# Microcontroller_STM32F101.net
KiCad netlist of a schematic drawn in Altium Designer
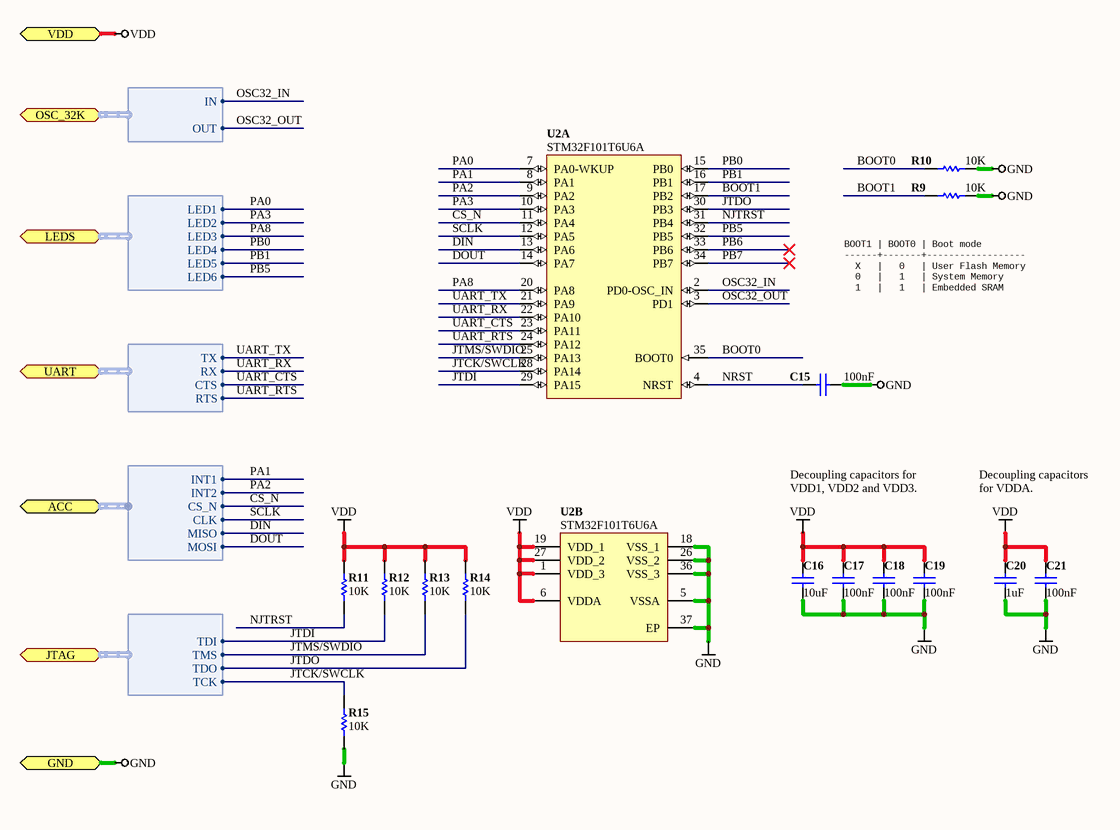
[diagram p0: Microcontroller_STM32F101.SchDoc]

(export (version "E")
  (design (tool "Eeschema 10.0.6"))
  (components
    (comp (ref "C15")
      (value "100nF")
      (footprint "CAPC0402(1005)60_N")
      (description "CAP 100nF 6.3V ±5% 0402 (1005 Metric) Thickness 0.6mm SMD")
      (fields (field (name "TOLERANCE") "±5%") (field (name "Comment") "CAP 100nF 6.3V 0402(1005)"))
      (libsource (lib "Altium Content Vault") (part "CMP-1034-02060-1"))
    )
    (comp (ref "C16")
      (value "10uF")
      (footprint "CAPC0603(1608)100_N")
      (description "CAP 10uF 10V ±20% 0603 (1608 Metric) Thickness 1mm SMD")
      (fields (field (name "TOLERANCE") "±20%") (field (name "Comment") "CAP 10uF 10V 0603(1608)"))
      (libsource (lib "Altium Content Vault") (part "CMP-1035-02800-1"))
    )
    (comp (ref "C17")
      (value "100nF")
      (footprint "CAPC0402(1005)60_N")
      (description "CAP 100nF 6.3V ±5% 0402 (1005 Metric) Thickness 0.6mm SMD")
      (fields (field (name "TOLERANCE") "±5%") (field (name "Comment") "CAP 100nF 6.3V 0402(1005)"))
      (libsource (lib "Altium Content Vault") (part "CMP-1034-02060-1"))
    )
    (comp (ref "C18")
      (value "100nF")
      (footprint "CAPC0402(1005)60_N")
      (description "CAP 100nF 6.3V ±5% 0402 (1005 Metric) Thickness 0.6mm SMD")
      (fields (field (name "TOLERANCE") "±5%") (field (name "Comment") "CAP 100nF 6.3V 0402(1005)"))
      (libsource (lib "Altium Content Vault") (part "CMP-1034-02060-1"))
    )
    (comp (ref "C19")
      (value "100nF")
      (footprint "CAPC0402(1005)60_N")
      (description "CAP 100nF 6.3V ±5% 0402 (1005 Metric) Thickness 0.6mm SMD")
      (fields (field (name "TOLERANCE") "±5%") (field (name "Comment") "CAP 100nF 6.3V 0402(1005)"))
      (libsource (lib "Altium Content Vault") (part "CMP-1034-02060-1"))
    )
    (comp (ref "C20")
      (value "1uF")
      (footprint "CAPC0402(1005)60_N")
      (description "CAP 1uF 6.3V ±10% 0402 (1005 Metric) Thickness 0.6mm SMD")
      (fields (field (name "TOLERANCE") "±10%") (field (name "Comment") "CAP 1uF 6.3V 0402(1005)"))
      (libsource (lib "Altium Content Vault") (part "CMP-1034-02113-1"))
    )
    (comp (ref "C21")
      (value "100nF")
      (footprint "CAPC0402(1005)60_N")
      (description "CAP 100nF 6.3V ±5% 0402 (1005 Metric) Thickness 0.6mm SMD")
      (fields (field (name "TOLERANCE") "±5%") (field (name "Comment") "CAP 100nF 6.3V 0402(1005)"))
      (libsource (lib "Altium Content Vault") (part "CMP-1034-02060-1"))
    )
    (comp (ref "R9")
      (value "10K")
      (footprint "RESC0402(1005)_N")
      (description "10K 0.063W 5% 0402 (1005 Metric)  SMD")
      (fields (field (name "TOLERANCE") "5 %") (field (name "POWER") "0.063 W"))
      (libsource (lib "Altium Content Vault") (part "CMP-1011-00098-1"))
    )
    (comp (ref "R10")
      (value "10K")
      (footprint "RESC0402(1005)_N")
      (description "10K 0.063W 5% 0402 (1005 Metric)  SMD")
      (fields (field (name "TOLERANCE") "5 %") (field (name "POWER") "0.063 W"))
      (libsource (lib "Altium Content Vault") (part "CMP-1011-00098-1"))
    )
    (comp (ref "R11")
      (value "10K")
      (footprint "RESC0402(1005)_N")
      (description "10K 0.063W 5% 0402 (1005 Metric)  SMD")
      (fields (field (name "TOLERANCE") "5 %") (field (name "POWER") "0.063 W"))
      (libsource (lib "Altium Content Vault") (part "CMP-1011-00098-1"))
    )
    (comp (ref "R12")
      (value "10K")
      (footprint "RESC0402(1005)_N")
      (description "10K 0.063W 5% 0402 (1005 Metric)  SMD")
      (fields (field (name "TOLERANCE") "5 %") (field (name "POWER") "0.063 W"))
      (libsource (lib "Altium Content Vault") (part "CMP-1011-00098-1"))
    )
    (comp (ref "R13")
      (value "10K")
      (footprint "RESC0402(1005)_N")
      (description "10K 0.063W 5% 0402 (1005 Metric)  SMD")
      (fields (field (name "TOLERANCE") "5 %") (field (name "POWER") "0.063 W"))
      (libsource (lib "Altium Content Vault") (part "CMP-1011-00098-1"))
    )
    (comp (ref "R14")
      (value "10K")
      (footprint "RESC0402(1005)_N")
      (description "10K 0.063W 5% 0402 (1005 Metric)  SMD")
      (fields (field (name "TOLERANCE") "5 %") (field (name "POWER") "0.063 W"))
      (libsource (lib "Altium Content Vault") (part "CMP-1011-00098-1"))
    )
    (comp (ref "R15")
      (value "10K")
      (footprint "RESC0402(1005)_N")
      (description "10K 0.063W 5% 0402 (1005 Metric)  SMD")
      (fields (field (name "TOLERANCE") "5 %") (field (name "POWER") "0.063 W"))
      (libsource (lib "Altium Content Vault") (part "CMP-1011-00098-1"))
    )
    (comp (ref "U2")
      (value "STM32F101T6U6A")
      (footprint "VFQFPN36_N")
      (libsource (lib "Altium Content Vault") (part "MC-ARM-STM32F101-SQ37"))
    )
  )
  (nets
    (net (code "6") (name "/BOOT0") (class "Default")
      (node (ref "R10") (pin "1") (pinfunction "1_1") (pintype "passive"))
      (node (ref "U2") (pin "35") (pinfunction "BOOT0_35") (pintype "input"))
    )
    (net (code "7") (name "/BOOT1") (class "Default")
      (node (ref "R9") (pin "1") (pinfunction "1_1") (pintype "passive"))
      (node (ref "U2") (pin "17") (pinfunction "PB2_17") (pintype "bidirectional"))
    )
    (net (code "8") (name "/CS_N") (class "Default")
      (node (ref "U2") (pin "11") (pinfunction "PA4_11") (pintype "bidirectional"))
    )
    (net (code "9") (name "/DIN") (class "Default")
      (node (ref "U2") (pin "13") (pinfunction "PA6_13") (pintype "bidirectional"))
    )
    (net (code "10") (name "/DOUT") (class "Default")
      (node (ref "U2") (pin "14") (pinfunction "PA7_14") (pintype "bidirectional"))
    )
    (net (code "11") (name "/JTCK{slash}SWCLK") (class "Default")
      (node (ref "R15") (pin "2") (pinfunction "2_2") (pintype "passive"))
      (node (ref "U2") (pin "28") (pinfunction "PA14_28") (pintype "bidirectional"))
    )
    (net (code "12") (name "/JTDI") (class "Default")
      (node (ref "R12") (pin "1") (pinfunction "1_1") (pintype "passive"))
      (node (ref "U2") (pin "29") (pinfunction "PA15_29") (pintype "bidirectional"))
    )
    (net (code "13") (name "/JTDO") (class "Default")
      (node (ref "R14") (pin "1") (pinfunction "1_1") (pintype "passive"))
      (node (ref "U2") (pin "30") (pinfunction "PB3_30") (pintype "bidirectional"))
    )
    (net (code "14") (name "/JTMS{slash}SWDIO") (class "Default")
      (node (ref "R13") (pin "1") (pinfunction "1_1") (pintype "passive"))
      (node (ref "U2") (pin "25") (pinfunction "PA13_25") (pintype "bidirectional"))
    )
    (net (code "15") (name "/NJTRST") (class "Default")
      (node (ref "R11") (pin "1") (pinfunction "1_1") (pintype "passive"))
      (node (ref "U2") (pin "31") (pinfunction "PB4_31") (pintype "bidirectional"))
    )
    (net (code "16") (name "/NRST") (class "Default")
      (node (ref "C15") (pin "1") (pinfunction "1_1") (pintype "passive"))
      (node (ref "U2") (pin "4") (pinfunction "NRST_4") (pintype "bidirectional"))
    )
    (net (code "17") (name "/OSC32_IN") (class "Default")
      (node (ref "U2") (pin "2") (pinfunction "PD0-OSC_IN_2") (pintype "bidirectional"))
    )
    (net (code "18") (name "/OSC32_OUT") (class "Default")
      (node (ref "U2") (pin "3") (pinfunction "PD1_3") (pintype "bidirectional"))
    )
    (net (code "19") (name "/PA0") (class "Default")
      (node (ref "U2") (pin "7") (pinfunction "PA0-WKUP_7") (pintype "bidirectional"))
    )
    (net (code "20") (name "/PA1") (class "Default")
      (node (ref "U2") (pin "8") (pinfunction "PA1_8") (pintype "bidirectional"))
    )
    (net (code "21") (name "/PA2") (class "Default")
      (node (ref "U2") (pin "9") (pinfunction "PA2_9") (pintype "bidirectional"))
    )
    (net (code "22") (name "/PA3") (class "Default")
      (node (ref "U2") (pin "10") (pinfunction "PA3_10") (pintype "bidirectional"))
    )
    (net (code "23") (name "/PA8") (class "Default")
      (node (ref "U2") (pin "20") (pinfunction "PA8_20") (pintype "bidirectional"))
    )
    (net (code "24") (name "/PB0") (class "Default")
      (node (ref "U2") (pin "15") (pinfunction "PB0_15") (pintype "bidirectional"))
    )
    (net (code "25") (name "/PB1") (class "Default")
      (node (ref "U2") (pin "16") (pinfunction "PB1_16") (pintype "bidirectional"))
    )
    (net (code "26") (name "/PB5") (class "Default")
      (node (ref "U2") (pin "32") (pinfunction "PB5_32") (pintype "bidirectional"))
    )
    (net (code "27") (name "/PB6") (class "Default")
      (node (ref "U2") (pin "33") (pinfunction "PB6_33") (pintype "bidirectional+no_connect"))
    )
    (net (code "28") (name "/PB7") (class "Default")
      (node (ref "U2") (pin "34") (pinfunction "PB7_34") (pintype "bidirectional+no_connect"))
    )
    (net (code "29") (name "/SCLK") (class "Default")
      (node (ref "U2") (pin "12") (pinfunction "PA5_12") (pintype "bidirectional"))
    )
    (net (code "30") (name "/UART_CTS") (class "Default")
      (node (ref "U2") (pin "23") (pinfunction "PA11_23") (pintype "bidirectional"))
    )
    (net (code "31") (name "/UART_RTS") (class "Default")
      (node (ref "U2") (pin "24") (pinfunction "PA12_24") (pintype "bidirectional"))
    )
    (net (code "32") (name "/UART_RX") (class "Default")
      (node (ref "U2") (pin "22") (pinfunction "PA10_22") (pintype "bidirectional"))
    )
    (net (code "33") (name "/UART_TX") (class "Default")
      (node (ref "U2") (pin "21") (pinfunction "PA9_21") (pintype "bidirectional"))
    )
    (net (code "39") (name "GND") (class "Default")
      (node (ref "C15") (pin "2") (pinfunction "2_2") (pintype "passive"))
      (node (ref "C16") (pin "1") (pinfunction "1_1") (pintype "passive"))
      (node (ref "C17") (pin "1") (pinfunction "1_1") (pintype "passive"))
      (node (ref "C18") (pin "1") (pinfunction "1_1") (pintype "passive"))
      (node (ref "C19") (pin "1") (pinfunction "1_1") (pintype "passive"))
      (node (ref "C20") (pin "1") (pinfunction "1_1") (pintype "passive"))
      (node (ref "C21") (pin "1") (pinfunction "1_1") (pintype "passive"))
      (node (ref "R10") (pin "2") (pinfunction "2_2") (pintype "passive"))
      (node (ref "R15") (pin "1") (pinfunction "1_1") (pintype "passive"))
      (node (ref "R9") (pin "2") (pinfunction "2_2") (pintype "passive"))
      (node (ref "U2") (pin "18") (pinfunction "VSS_1_18") (pintype "power_in"))
      (node (ref "U2") (pin "26") (pinfunction "VSS_2_26") (pintype "power_in"))
      (node (ref "U2") (pin "36") (pinfunction "VSS_3_36") (pintype "power_in"))
      (node (ref "U2") (pin "37") (pinfunction "EP_37") (pintype "power_in"))
      (node (ref "U2") (pin "5") (pinfunction "VSSA_5") (pintype "power_in"))
    )
    (net (code "40") (name "VDD") (class "Default")
      (node (ref "C16") (pin "2") (pinfunction "2_2") (pintype "passive"))
      (node (ref "C17") (pin "2") (pinfunction "2_2") (pintype "passive"))
      (node (ref "C18") (pin "2") (pinfunction "2_2") (pintype "passive"))
      (node (ref "C19") (pin "2") (pinfunction "2_2") (pintype "passive"))
      (node (ref "C20") (pin "2") (pinfunction "2_2") (pintype "passive"))
      (node (ref "C21") (pin "2") (pinfunction "2_2") (pintype "passive"))
      (node (ref "R11") (pin "2") (pinfunction "2_2") (pintype "passive"))
      (node (ref "R12") (pin "2") (pinfunction "2_2") (pintype "passive"))
      (node (ref "R13") (pin "2") (pinfunction "2_2") (pintype "passive"))
      (node (ref "R14") (pin "2") (pinfunction "2_2") (pintype "passive"))
      (node (ref "U2") (pin "1") (pinfunction "VDD_3_1") (pintype "power_in"))
      (node (ref "U2") (pin "19") (pinfunction "VDD_1_19") (pintype "power_in"))
      (node (ref "U2") (pin "27") (pinfunction "VDD_2_27") (pintype "power_in"))
      (node (ref "U2") (pin "6") (pinfunction "VDDA_6") (pintype "power_in"))
    )
  )
)
